# current-sense-v1_0.net
KiCad netlist of a schematic drawn in EAGLE
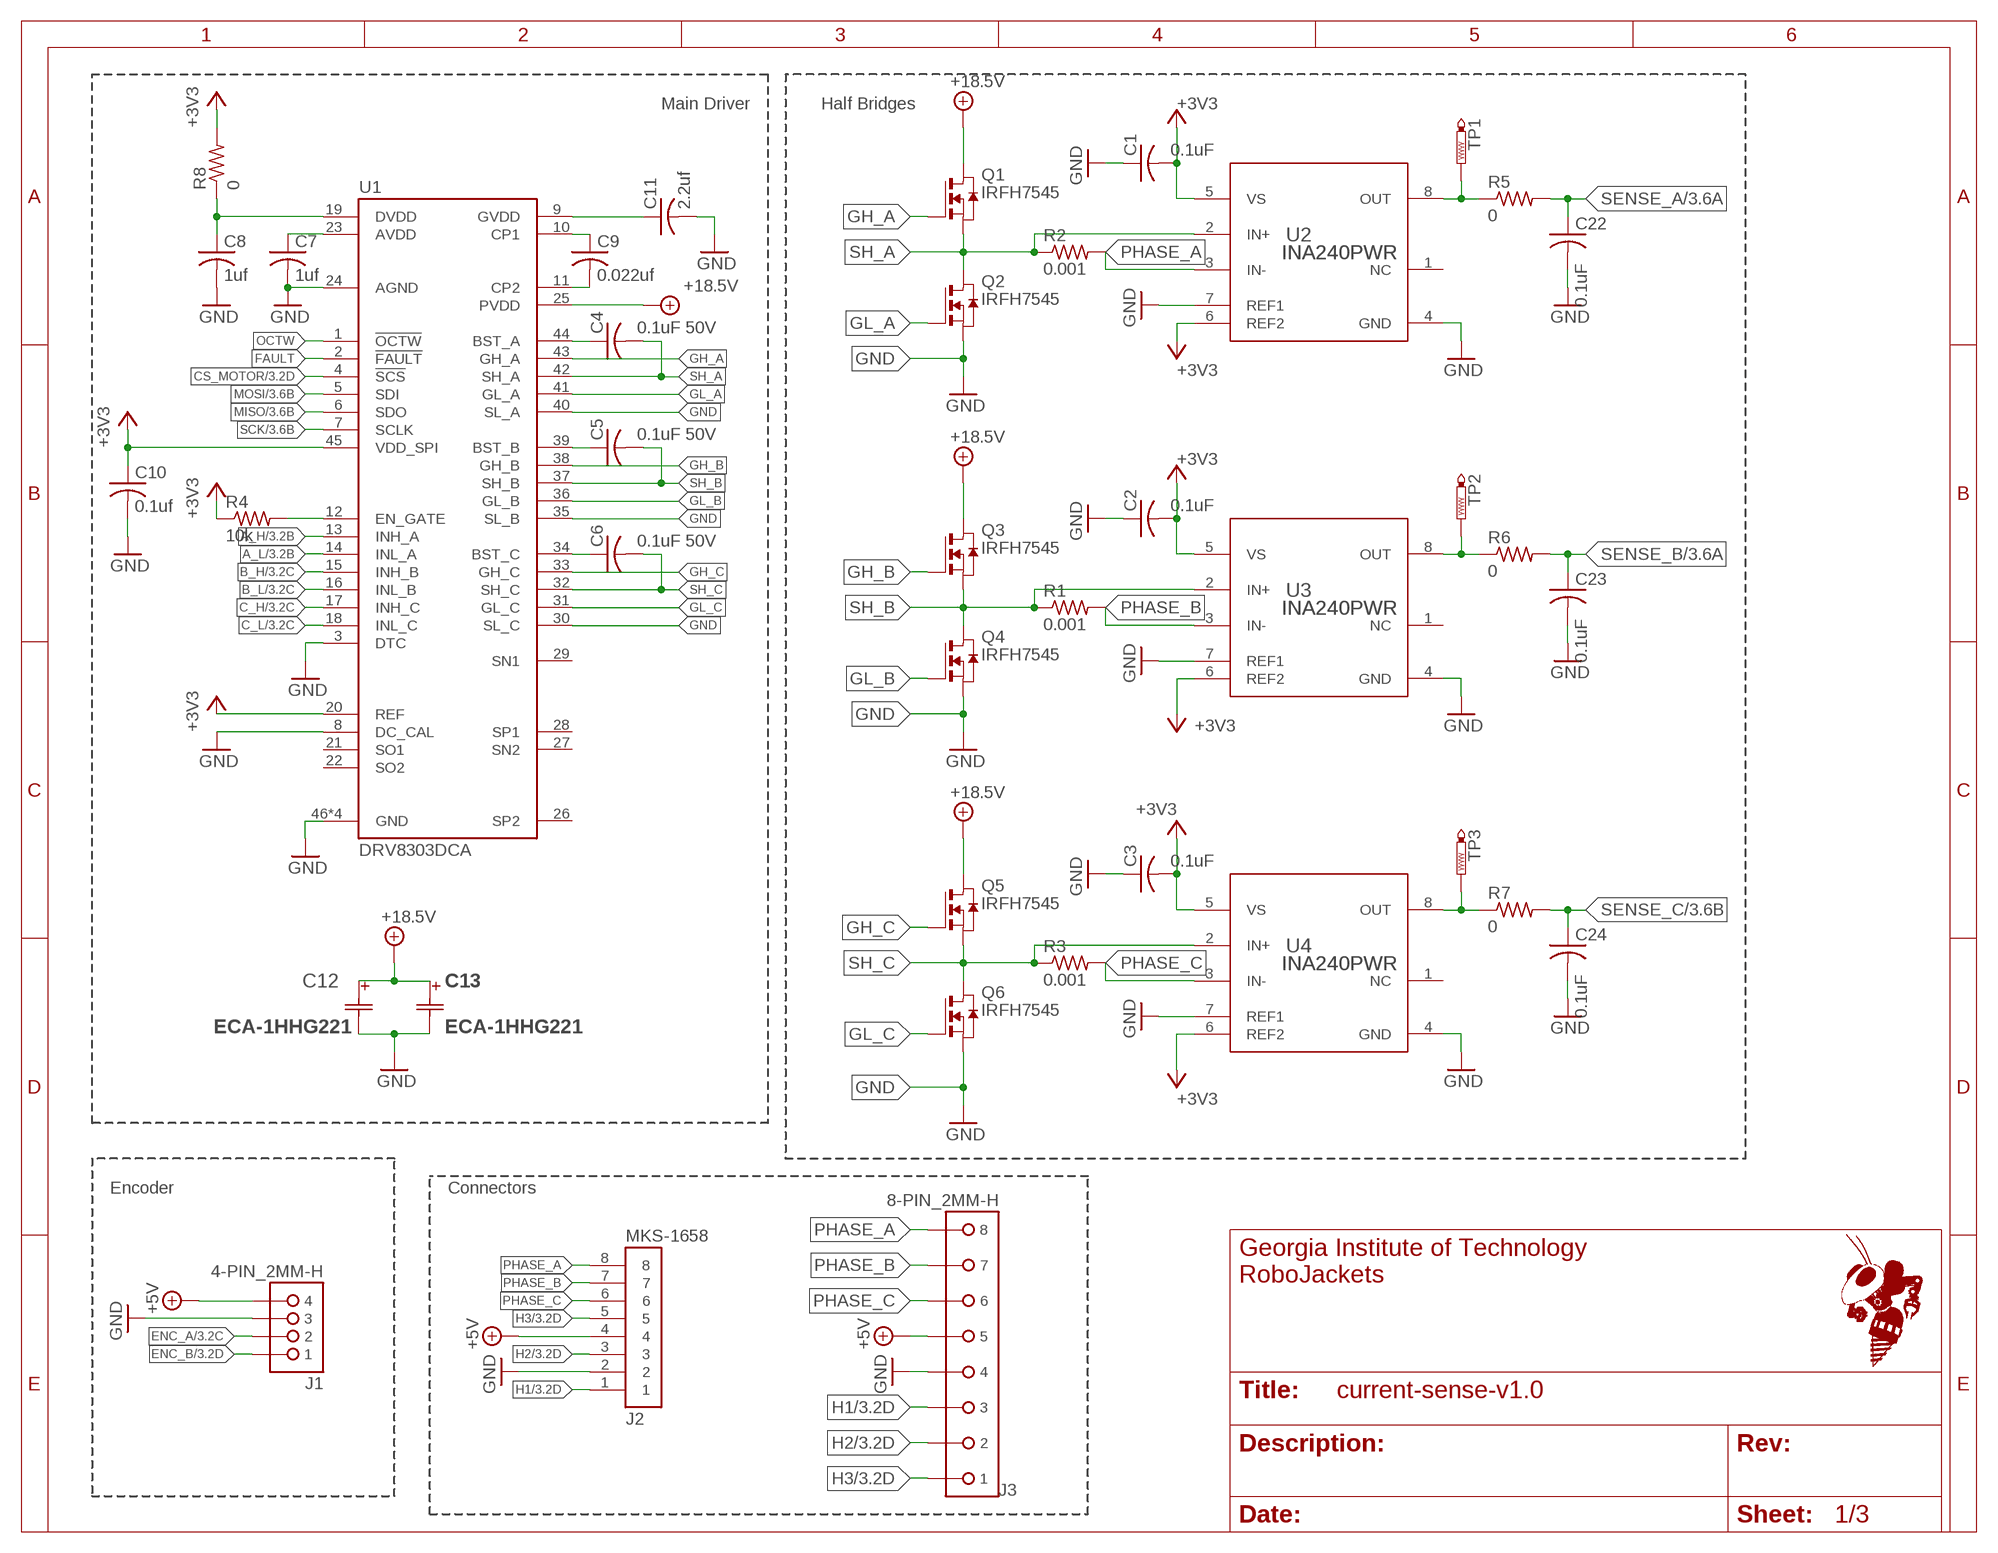
[diagram p0: schematic, sheet 1]
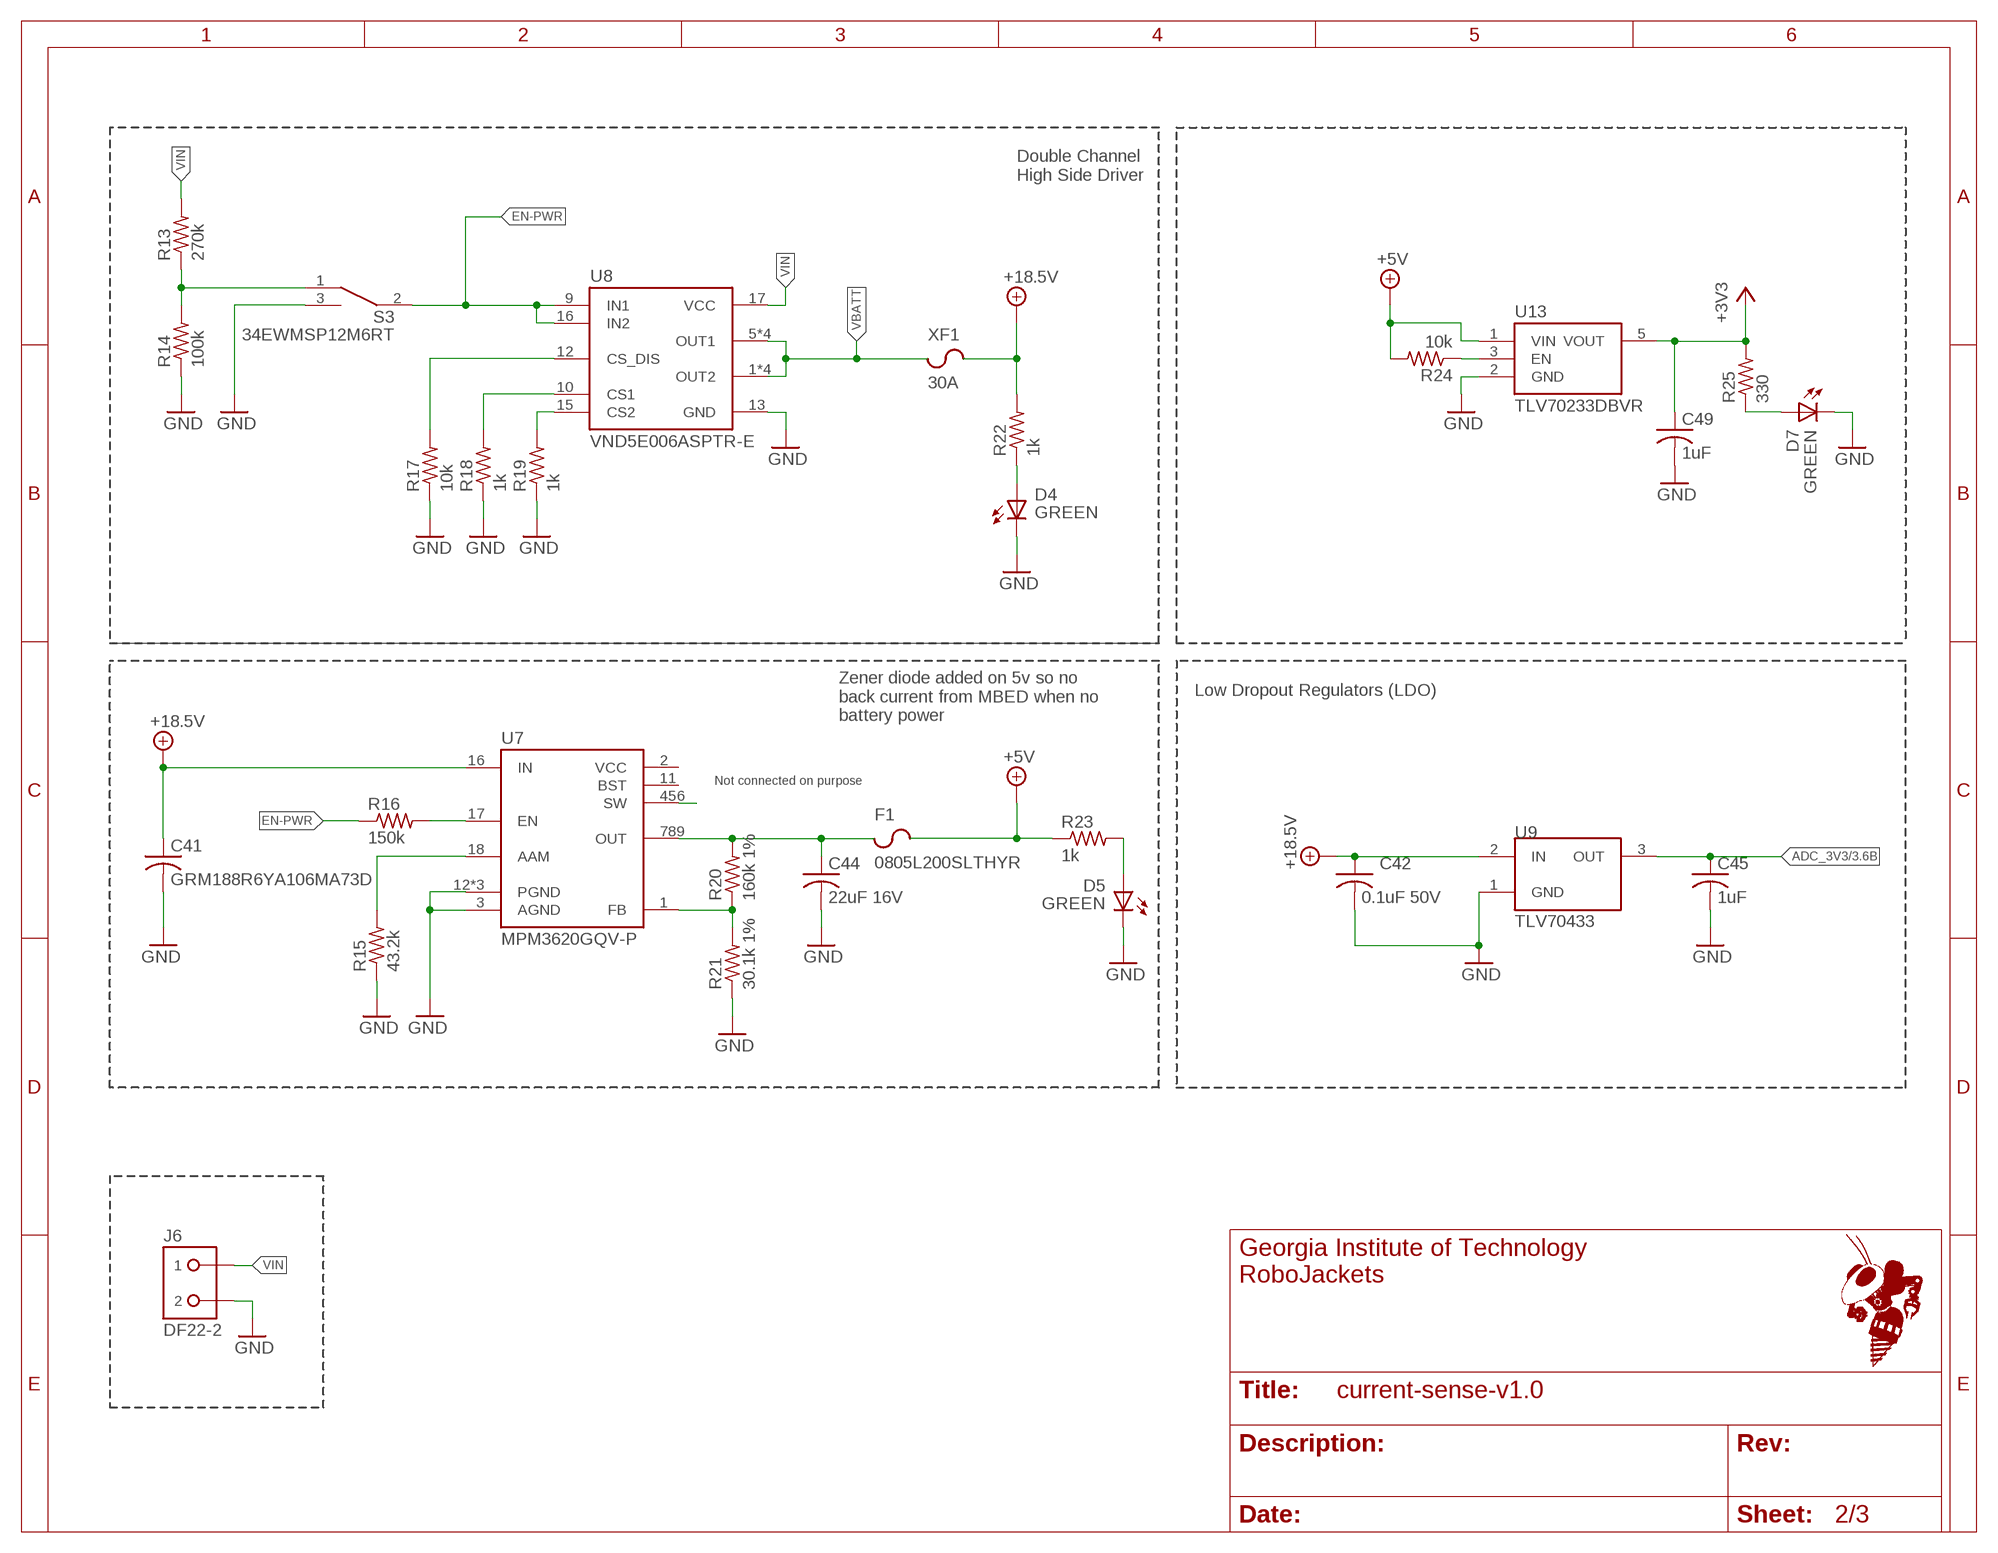
[diagram p1: schematic, sheet 2]
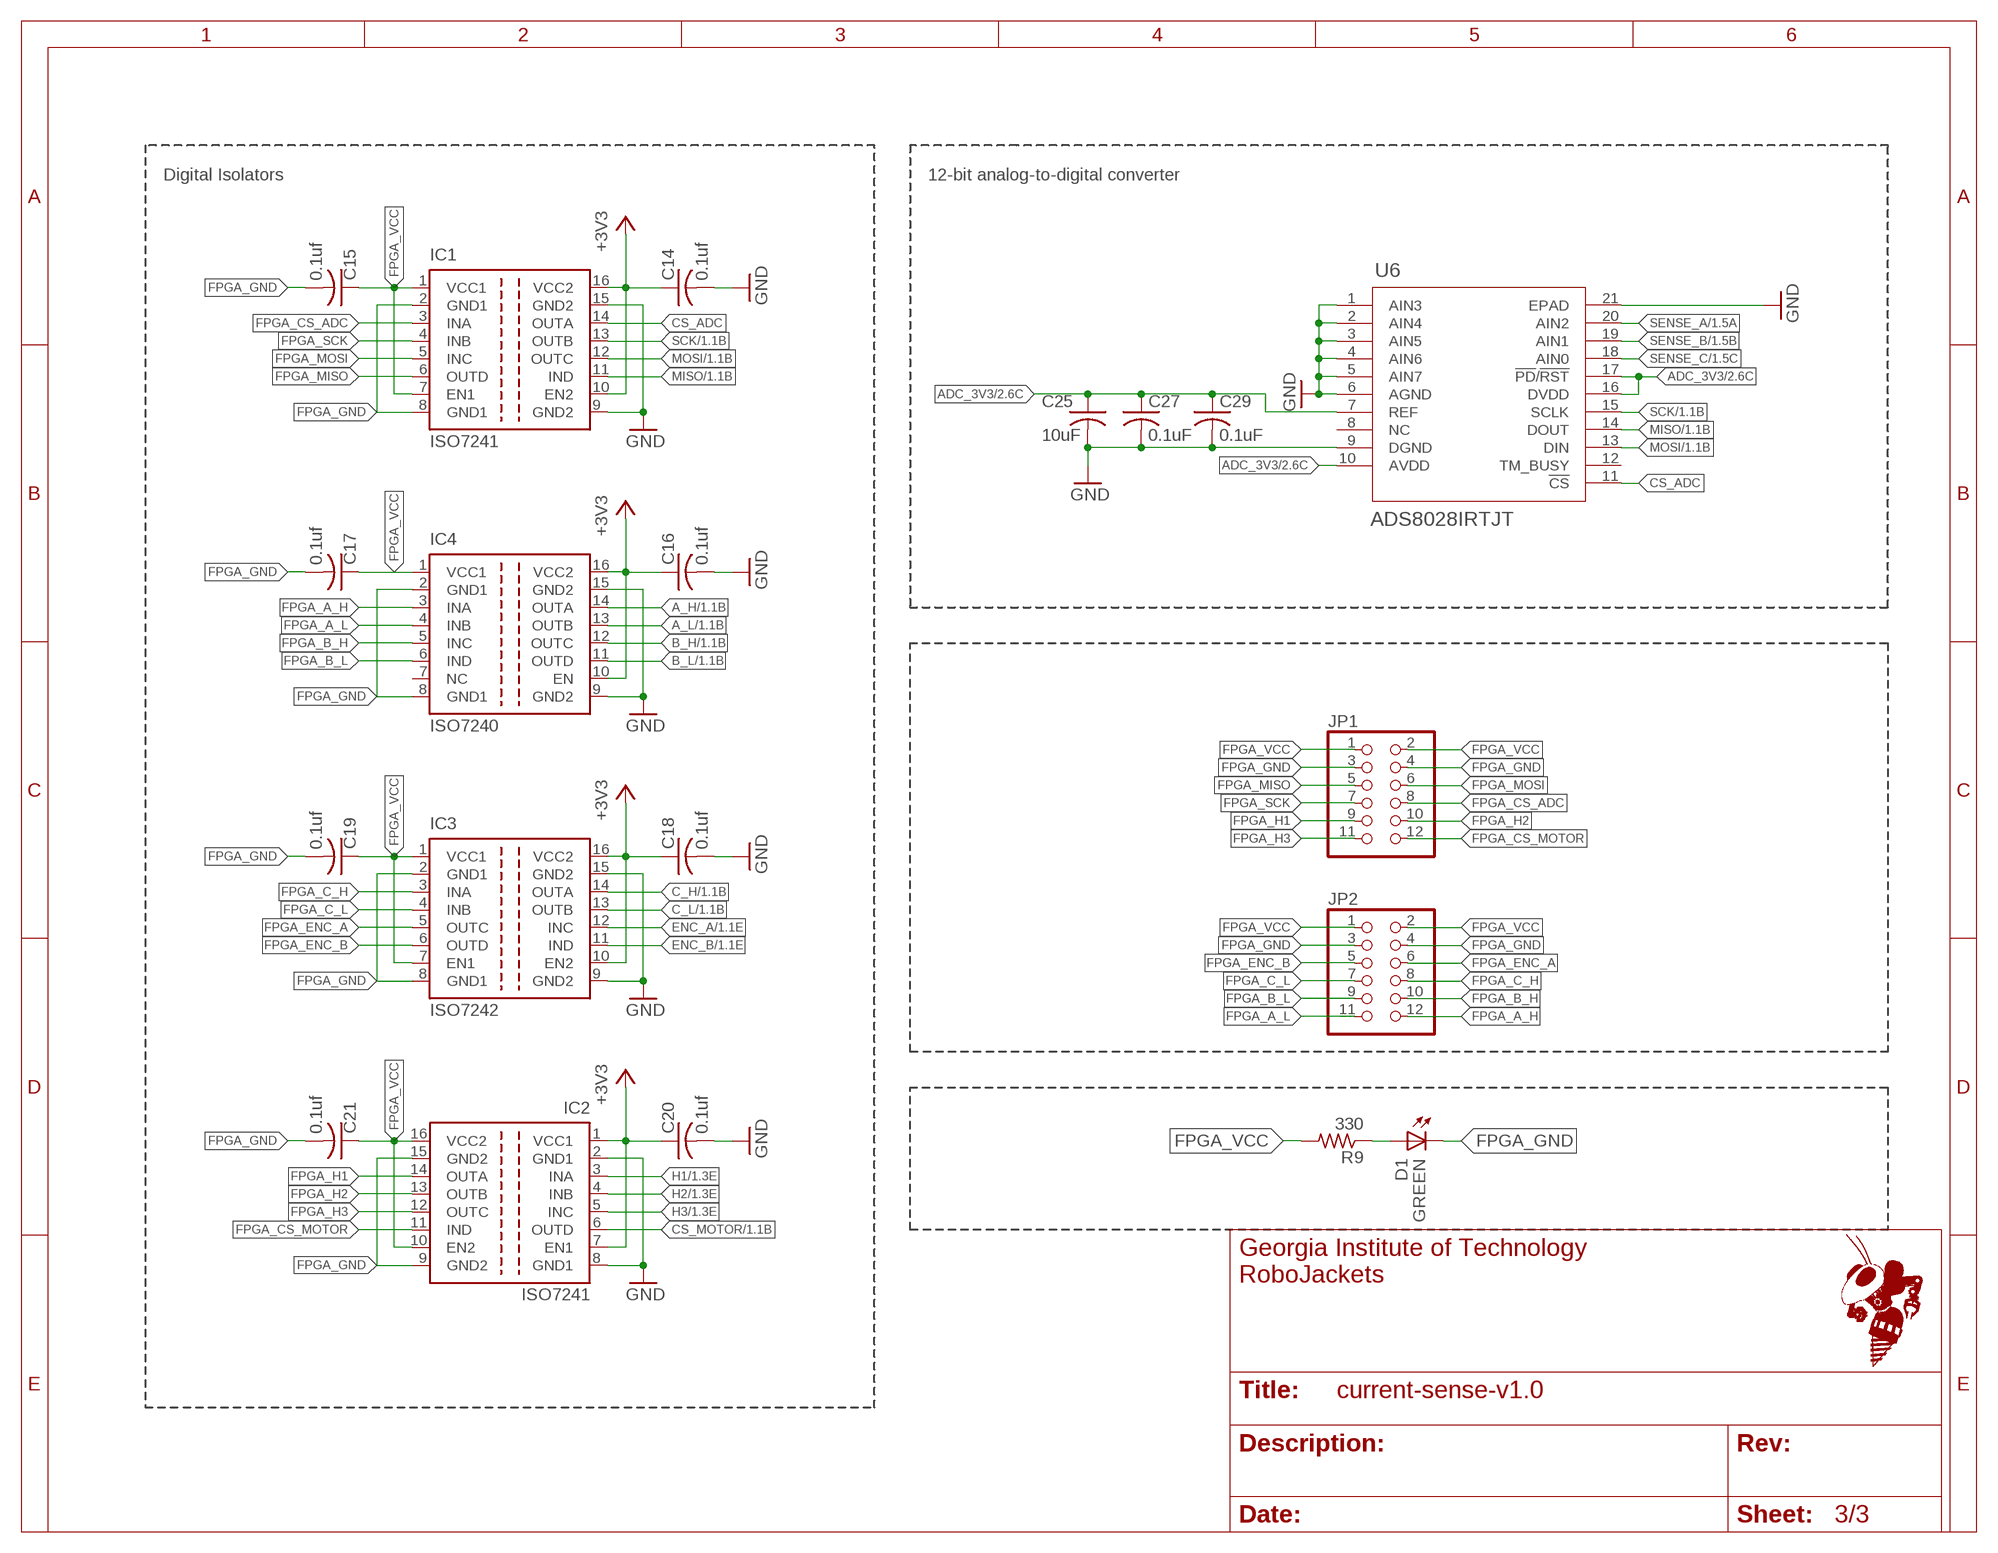
[diagram p2: schematic, sheet 3]

(export (version "E")
  (design (tool "Eeschema 10.0.6"))
  (components
    (comp (ref "C14")
      (value "0.1uf")
      (footprint "eagle-import:C0603")
      (libsource (lib "eagle-import") (part "rcl_334_C-USC0603"))
    )
    (comp (ref "C15")
      (value "0.1uf")
      (footprint "eagle-import:C0603")
      (libsource (lib "eagle-import") (part "rcl_334_C-USC0603"))
    )
    (comp (ref "C16")
      (value "0.1uf")
      (footprint "eagle-import:C0603")
      (libsource (lib "eagle-import") (part "rcl_334_C-USC0603"))
    )
    (comp (ref "C17")
      (value "0.1uf")
      (footprint "eagle-import:C0603")
      (libsource (lib "eagle-import") (part "rcl_334_C-USC0603"))
    )
    (comp (ref "C18")
      (value "0.1uf")
      (footprint "eagle-import:C0603")
      (libsource (lib "eagle-import") (part "rcl_334_C-USC0603"))
    )
    (comp (ref "C19")
      (value "0.1uf")
      (footprint "eagle-import:C0603")
      (libsource (lib "eagle-import") (part "rcl_334_C-USC0603"))
    )
    (comp (ref "C20")
      (value "0.1uf")
      (footprint "eagle-import:C0603")
      (libsource (lib "eagle-import") (part "rcl_334_C-USC0603"))
    )
    (comp (ref "C21")
      (value "0.1uf")
      (footprint "eagle-import:C0603")
      (libsource (lib "eagle-import") (part "rcl_334_C-USC0603"))
    )
    (comp (ref "C25")
      (value "10uF")
      (footprint "eagle-import:C0603")
      (libsource (lib "eagle-import") (part "rcl_334_C-USC0603"))
    )
    (comp (ref "C27")
      (value "0.1uF")
      (footprint "eagle-import:C0603")
      (libsource (lib "eagle-import") (part "rcl_334_C-USC0603"))
    )
    (comp (ref "C29")
      (value "0.1uF")
      (footprint "eagle-import:C0603")
      (libsource (lib "eagle-import") (part "rcl_334_C-USC0603"))
    )
    (comp (ref "D1")
      (value "GREEN")
      (footprint "eagle-import:CHIP-LED0603")
      (fields (field (name "MPN") "LTST-C191KGKT"))
      (libsource (lib "eagle-import") (part "LED-SMD-GREEN"))
    )
    (comp (ref "IC1")
      (value "ISO7241")
      (footprint "eagle-import:SO-16DW")
      (fields (field (name "MPN") "ISO7241CDW"))
      (libsource (lib "eagle-import") (part "ISO7241"))
    )
    (comp (ref "IC2")
      (value "ISO7241")
      (footprint "eagle-import:SO-16DW")
      (fields (field (name "MPN") "ISO7241CDW"))
      (libsource (lib "eagle-import") (part "ISO7241"))
    )
    (comp (ref "IC3")
      (value "ISO7242")
      (footprint "eagle-import:SO-16DW")
      (fields (field (name "MPN") "ISO7242MDW"))
      (libsource (lib "eagle-import") (part "ISO7242"))
    )
    (comp (ref "IC4")
      (value "ISO7240")
      (footprint "eagle-import:SO-16DW")
      (fields (field (name "MPN") "ISO7240MDW"))
      (libsource (lib "eagle-import") (part "ISO7240"))
    )
    (comp (ref "JP1")
      (value "PINHD-2X6/90")
      (footprint "eagle-import:2X06_90")
      (libsource (lib "eagle-import") (part "PINHD-2X6/90"))
    )
    (comp (ref "JP2")
      (value "PINHD-2X6/90")
      (footprint "eagle-import:2X06_90")
      (libsource (lib "eagle-import") (part "PINHD-2X6/90"))
    )
    (comp (ref "R9")
      (value "330")
      (footprint "eagle-import:R0603")
      (libsource (lib "eagle-import") (part "resistor_348_R-US_R0603"))
    )
    (comp (ref "U6")
      (value "ADS8028IRTJT")
      (footprint "eagle-import:RTJ20_2P7X2P7")
      (libsource (lib "eagle-import") (part "ADS8028IRTJT"))
    )
    (comp (ref "C1")
      (value "0.1uF")
      (footprint "eagle-import:C0603")
      (libsource (lib "eagle-import") (part "rcl_334_C-USC0603"))
    )
    (comp (ref "C2")
      (value "0.1uF")
      (footprint "eagle-import:C0603")
      (libsource (lib "eagle-import") (part "rcl_334_C-USC0603"))
    )
    (comp (ref "C3")
      (value "0.1uF")
      (footprint "eagle-import:C0603")
      (libsource (lib "eagle-import") (part "rcl_334_C-USC0603"))
    )
    (comp (ref "C4")
      (value "0.1uF 50V")
      (footprint "eagle-import:C0603")
      (libsource (lib "eagle-import") (part "rcl_334_C-USC0603"))
    )
    (comp (ref "C5")
      (value "0.1uF 50V")
      (footprint "eagle-import:C0603")
      (libsource (lib "eagle-import") (part "rcl_334_C-USC0603"))
    )
    (comp (ref "C6")
      (value "0.1uF 50V")
      (footprint "eagle-import:C0603")
      (libsource (lib "eagle-import") (part "rcl_334_C-USC0603"))
    )
    (comp (ref "C7")
      (value "1uf")
      (footprint "eagle-import:C0603")
      (libsource (lib "eagle-import") (part "rcl_334_C-USC0603"))
    )
    (comp (ref "C8")
      (value "1uf")
      (footprint "eagle-import:C0603")
      (libsource (lib "eagle-import") (part "rcl_334_C-USC0603"))
    )
    (comp (ref "C9")
      (value "0.022uf")
      (footprint "eagle-import:C0603")
      (libsource (lib "eagle-import") (part "rcl_334_C-USC0603"))
    )
    (comp (ref "C10")
      (value "0.1uf")
      (footprint "eagle-import:C0603")
      (libsource (lib "eagle-import") (part "rcl_334_C-USC0603"))
    )
    (comp (ref "C11")
      (value "2.2uf")
      (footprint "eagle-import:C0603")
      (libsource (lib "eagle-import") (part "rcl_334_C-USC0603"))
    )
    (comp (ref "C12")
      (value "ECA-1HHG221")
      (footprint "eagle-import:CAP_PAN_10X12.5")
      (libsource (lib "eagle-import") (part "ECA-1HHG221"))
    )
    (comp (ref "C13")
      (value "ECA-1HHG221")
      (footprint "eagle-import:CAP_PAN_10X12.5")
      (libsource (lib "eagle-import") (part "ECA-1HHG221"))
    )
    (comp (ref "C22")
      (value "0.1uF")
      (footprint "eagle-import:C0603")
      (libsource (lib "eagle-import") (part "rcl_334_C-USC0603"))
    )
    (comp (ref "C23")
      (value "0.1uF")
      (footprint "eagle-import:C0603")
      (libsource (lib "eagle-import") (part "rcl_334_C-USC0603"))
    )
    (comp (ref "C24")
      (value "0.1uF")
      (footprint "eagle-import:C0603")
      (libsource (lib "eagle-import") (part "rcl_334_C-USC0603"))
    )
    (comp (ref "J1")
      (value "4-PIN_2MM-H")
      (footprint "eagle-import:2MM-4-H")
      (fields (field (name "MPN") "0353630460"))
      (libsource (lib "eagle-import") (part "4-PIN_2MM-H"))
    )
    (comp (ref "J2")
      (value "MKS-1658")
      (footprint "eagle-import:MKS-1658")
      (fields (field (name "MPN") "MKS 1658-6-0-808"))
      (libsource (lib "eagle-import") (part "MKS-1658"))
    )
    (comp (ref "J3")
      (value "8-PIN_2MM-H")
      (footprint "eagle-import:2MM-8-H")
      (fields (field (name "MPN") "0353630860"))
      (libsource (lib "eagle-import") (part "8-PIN_2MM-H"))
    )
    (comp (ref "Q1")
      (value "IRFH7545")
      (footprint "eagle-import:PQFN_5X6_E")
      (fields (field (name "MPN") "IRFH7545TRPBF"))
      (libsource (lib "eagle-import") (part "IRFH7545"))
    )
    (comp (ref "Q2")
      (value "IRFH7545")
      (footprint "eagle-import:PQFN_5X6_E")
      (fields (field (name "MPN") "IRFH7545TRPBF"))
      (libsource (lib "eagle-import") (part "IRFH7545"))
    )
    (comp (ref "Q3")
      (value "IRFH7545")
      (footprint "eagle-import:PQFN_5X6_E")
      (fields (field (name "MPN") "IRFH7545TRPBF"))
      (libsource (lib "eagle-import") (part "IRFH7545"))
    )
    (comp (ref "Q4")
      (value "IRFH7545")
      (footprint "eagle-import:PQFN_5X6_E")
      (fields (field (name "MPN") "IRFH7545TRPBF"))
      (libsource (lib "eagle-import") (part "IRFH7545"))
    )
    (comp (ref "Q5")
      (value "IRFH7545")
      (footprint "eagle-import:PQFN_5X6_E")
      (fields (field (name "MPN") "IRFH7545TRPBF"))
      (libsource (lib "eagle-import") (part "IRFH7545"))
    )
    (comp (ref "Q6")
      (value "IRFH7545")
      (footprint "eagle-import:PQFN_5X6_E")
      (fields (field (name "MPN") "IRFH7545TRPBF"))
      (libsource (lib "eagle-import") (part "IRFH7545"))
    )
    (comp (ref "R1")
      (value "0.001")
      (footprint "eagle-import:R2512")
      (libsource (lib "eagle-import") (part "rcl_334_R-US_R2512"))
    )
    (comp (ref "R2")
      (value "0.001")
      (footprint "eagle-import:R2512")
      (libsource (lib "eagle-import") (part "rcl_334_R-US_R2512"))
    )
    (comp (ref "R3")
      (value "0.001")
      (footprint "eagle-import:R2512")
      (libsource (lib "eagle-import") (part "rcl_334_R-US_R2512"))
    )
    (comp (ref "R4")
      (value "10k")
      (footprint "eagle-import:R0603")
      (libsource (lib "eagle-import") (part "rcl_334_R-US_R0603"))
    )
    (comp (ref "R5")
      (value "0")
      (footprint "eagle-import:R0603")
      (libsource (lib "eagle-import") (part "rcl_334_R-US_R0603"))
    )
    (comp (ref "R6")
      (value "0")
      (footprint "eagle-import:R0603")
      (libsource (lib "eagle-import") (part "rcl_334_R-US_R0603"))
    )
    (comp (ref "R7")
      (value "0")
      (footprint "eagle-import:R0603")
      (libsource (lib "eagle-import") (part "rcl_334_R-US_R0603"))
    )
    (comp (ref "R8")
      (value "0")
      (footprint "eagle-import:R0603")
      (libsource (lib "eagle-import") (part "rcl_334_R-US_R0603"))
    )
    (comp (ref "TP1")
      (value "PTR1PAD1-13")
      (footprint "eagle-import:P1-13")
      (libsource (lib "eagle-import") (part "PTR1PAD1-13"))
    )
    (comp (ref "TP2")
      (value "PTR1PAD1-13")
      (footprint "eagle-import:P1-13")
      (libsource (lib "eagle-import") (part "PTR1PAD1-13"))
    )
    (comp (ref "TP3")
      (value "PTR1PAD1-13")
      (footprint "eagle-import:P1-13")
      (libsource (lib "eagle-import") (part "PTR1PAD1-13"))
    )
    (comp (ref "U1")
      (value "DRV8303DCA")
      (footprint "eagle-import:TSSOP-48_PAD")
      (fields (field (name "MPN") "DRV8303DCAR"))
      (libsource (lib "eagle-import") (part "DRV8303DCA"))
    )
    (comp (ref "U2")
      (value "INA240PWR")
      (footprint "eagle-import:PW0008A_N")
      (libsource (lib "eagle-import") (part "INA240PWR"))
    )
    (comp (ref "U3")
      (value "INA240PWR")
      (footprint "eagle-import:PW0008A_N")
      (libsource (lib "eagle-import") (part "INA240PWR"))
    )
    (comp (ref "U4")
      (value "INA240PWR")
      (footprint "eagle-import:PW0008A_N")
      (libsource (lib "eagle-import") (part "INA240PWR"))
    )
    (comp (ref "C41")
      (value "GRM188R6YA106MA73D")
      (footprint "eagle-import:C0603")
      (libsource (lib "eagle-import") (part "C-USC0603"))
    )
    (comp (ref "C42")
      (value "0.1uF 50V")
      (footprint "eagle-import:C0603")
      (libsource (lib "eagle-import") (part "rcl_334_C-USC0603"))
    )
    (comp (ref "C44")
      (value "22uF 16V")
      (footprint "eagle-import:C0805")
      (libsource (lib "eagle-import") (part "rcl_334_C-USC0805"))
    )
    (comp (ref "C45")
      (value "1uF")
      (footprint "eagle-import:C0603")
      (libsource (lib "eagle-import") (part "rcl_334_C-USC0603"))
    )
    (comp (ref "C49")
      (value "1uF")
      (footprint "eagle-import:C0603")
      (libsource (lib "eagle-import") (part "C-USC0603"))
    )
    (comp (ref "D4")
      (value "GREEN")
      (footprint "eagle-import:CHIP-LED0603")
      (fields (field (name "MPN") "LTST-C191KGKT"))
      (libsource (lib "eagle-import") (part "LED-SMD-GREEN"))
    )
    (comp (ref "D5")
      (value "GREEN")
      (footprint "eagle-import:CHIP-LED0603")
      (fields (field (name "MPN") "LTST-C191KGKT"))
      (libsource (lib "eagle-import") (part "LED-SMD-GREEN"))
    )
    (comp (ref "D7")
      (value "GREEN")
      (footprint "eagle-import:CHIP-LED0603")
      (fields (field (name "MPN") "LTST-C191KGKT"))
      (libsource (lib "eagle-import") (part "LED-SMD-GREEN"))
    )
    (comp (ref "F1")
      (value "0805L200SLTHYR")
      (footprint "eagle-import:FUSC2113X75")
      (libsource (lib "eagle-import") (part "CHIP_FUSE0805"))
    )
    (comp (ref "J6")
      (value "DF22-2")
      (footprint "eagle-import:DF22-2-H")
      (fields (field (name "MPN") "DF22-2P-7.92DS(35)"))
      (libsource (lib "eagle-import") (part "DF22-2"))
    )
    (comp (ref "R13")
      (value "270k")
      (footprint "eagle-import:R0603")
      (libsource (lib "eagle-import") (part "R-US_R0603"))
    )
    (comp (ref "R14")
      (value "100k")
      (footprint "eagle-import:R0603")
      (libsource (lib "eagle-import") (part "R-US_R0603"))
    )
    (comp (ref "R15")
      (value "43.2k")
      (footprint "eagle-import:R0603")
      (libsource (lib "eagle-import") (part "rcl_334_R-US_R0603"))
    )
    (comp (ref "R16")
      (value "150k")
      (footprint "eagle-import:R0603")
      (libsource (lib "eagle-import") (part "rcl_334_R-US_R0603"))
    )
    (comp (ref "R17")
      (value "10k")
      (footprint "eagle-import:R0603")
      (libsource (lib "eagle-import") (part "R-US_R0603"))
    )
    (comp (ref "R18")
      (value "1k")
      (footprint "eagle-import:R0603")
      (libsource (lib "eagle-import") (part "R-US_R0603"))
    )
    (comp (ref "R19")
      (value "1k")
      (footprint "eagle-import:R0603")
      (libsource (lib "eagle-import") (part "R-US_R0603"))
    )
    (comp (ref "R20")
      (value "160k 1%")
      (footprint "eagle-import:R0603")
      (libsource (lib "eagle-import") (part "rcl_334_R-US_R0603"))
    )
    (comp (ref "R21")
      (value "30.1k 1%")
      (footprint "eagle-import:R0603")
      (libsource (lib "eagle-import") (part "rcl_334_R-US_R0603"))
    )
    (comp (ref "R22")
      (value "1k")
      (footprint "eagle-import:R0603")
      (libsource (lib "eagle-import") (part "R-US_R0603"))
    )
    (comp (ref "R23")
      (value "1k")
      (footprint "eagle-import:R0603")
      (libsource (lib "eagle-import") (part "resistor_348_R-US_R0603"))
    )
    (comp (ref "R24")
      (value "10k")
      (footprint "eagle-import:R0603")
      (libsource (lib "eagle-import") (part "R-US_R0603"))
    )
    (comp (ref "R25")
      (value "330")
      (footprint "eagle-import:R0603")
      (libsource (lib "eagle-import") (part "resistor_348_R-US_R0603"))
    )
    (comp (ref "S3")
      (value "34EWMSP12M6RT")
      (footprint "eagle-import:34EWMSP12M6RT")
      (libsource (lib "eagle-import") (part "34EWMSP12M6RT"))
    )
    (comp (ref "U7")
      (value "MPM3620GQV-P")
      (footprint "eagle-import:MPM3620GQV-P")
      (libsource (lib "eagle-import") (part "MPM3620GQV-P"))
    )
    (comp (ref "U8")
      (value "VND5E006ASPTR-E")
      (footprint "eagle-import:POWERSO-16")
      (libsource (lib "eagle-import") (part "VND5E006ASPTR-E"))
    )
    (comp (ref "U9")
      (value "TLV70433")
      (footprint "eagle-import:SOT-23-5")
      (libsource (lib "eagle-import") (part "TLV70433"))
    )
    (comp (ref "U13")
      (value "TLV70233DBVR")
      (footprint "eagle-import:SOT-23-5")
      (libsource (lib "eagle-import") (part "TLV70233DBVR"))
    )
    (comp (ref "XF1")
      (value "30A")
      (footprint "eagle-import:3557-2")
      (fields (field (name "MPN") "3557-2"))
      (libsource (lib "eagle-import") (part "3557-2"))
    )
  )
  (nets
    (net (code "1") (name "+3V3") (class "Default")
      (node (ref "C1") (pin "2") (pinfunction "2_2") (pintype "passive"))
      (node (ref "C10") (pin "1") (pinfunction "1_1") (pintype "passive"))
      (node (ref "C14") (pin "1") (pinfunction "1_1") (pintype "passive"))
      (node (ref "C16") (pin "1") (pinfunction "1_1") (pintype "passive"))
      (node (ref "C18") (pin "1") (pinfunction "1_1") (pintype "passive"))
      (node (ref "C2") (pin "2") (pinfunction "2_2") (pintype "passive"))
      (node (ref "C20") (pin "1") (pinfunction "1_1") (pintype "passive"))
      (node (ref "C3") (pin "2") (pinfunction "2_2") (pintype "passive"))
      (node (ref "C49") (pin "1") (pinfunction "1_1") (pintype "passive"))
      (node (ref "IC1") (pin "10") (pinfunction "EN2_10") (pintype "input"))
      (node (ref "IC1") (pin "16") (pinfunction "VCC2_16") (pintype "power_in"))
      (node (ref "IC2") (pin "1") (pinfunction "VCC1_1") (pintype "power_in"))
      (node (ref "IC2") (pin "7") (pinfunction "EN1_7") (pintype "input"))
      (node (ref "IC3") (pin "10") (pinfunction "EN2_10") (pintype "input"))
      (node (ref "IC3") (pin "16") (pinfunction "VCC2_16") (pintype "power_in"))
      (node (ref "IC4") (pin "10") (pinfunction "EN_10") (pintype "input"))
      (node (ref "IC4") (pin "16") (pinfunction "VCC2_16") (pintype "power_in"))
      (node (ref "R25") (pin "2") (pinfunction "2_2") (pintype "passive"))
      (node (ref "R4") (pin "1") (pinfunction "1_1") (pintype "passive"))
      (node (ref "R8") (pin "2") (pinfunction "2_2") (pintype "passive"))
      (node (ref "U1") (pin "20") (pinfunction "REF_20") (pintype "bidirectional"))
      (node (ref "U1") (pin "45") (pinfunction "VDD_SPI_45") (pintype "bidirectional"))
      (node (ref "U13") (pin "5") (pinfunction "VOUT_5") (pintype "bidirectional"))
      (node (ref "U2") (pin "5") (pinfunction "VS_5") (pintype "power_in"))
      (node (ref "U2") (pin "6") (pinfunction "REF2_6") (pintype "input"))
      (node (ref "U3") (pin "5") (pinfunction "VS_5") (pintype "power_in"))
      (node (ref "U3") (pin "6") (pinfunction "REF2_6") (pintype "input"))
      (node (ref "U4") (pin "5") (pinfunction "VS_5") (pintype "power_in"))
      (node (ref "U4") (pin "6") (pinfunction "REF2_6") (pintype "input"))
    )
    (net (code "2") (name "+5V") (class "Default")
      (node (ref "F1") (pin "2") (pinfunction "2_2") (pintype "bidirectional"))
      (node (ref "J1") (pin "4") (pinfunction "4_4") (pintype "passive"))
      (node (ref "J2") (pin "4") (pinfunction "4_4") (pintype "bidirectional"))
      (node (ref "J3") (pin "5") (pinfunction "5_5") (pintype "passive"))
      (node (ref "R23") (pin "1") (pinfunction "1_1") (pintype "passive"))
      (node (ref "R24") (pin "2") (pinfunction "2_2") (pintype "passive"))
      (node (ref "U13") (pin "1") (pinfunction "VIN_1") (pintype "bidirectional"))
    )
    (net (code "3") (name "+18.5V") (class "Default")
      (node (ref "C12") (pin "1") (pinfunction "11_1") (pintype "passive"))
      (node (ref "C13") (pin "1") (pinfunction "11_1") (pintype "passive"))
      (node (ref "C41") (pin "1") (pinfunction "1_1") (pintype "passive"))
      (node (ref "C42") (pin "1") (pinfunction "1_1") (pintype "passive"))
      (node (ref "Q1") (pin "5678") (pinfunction "D_5678") (pintype "passive"))
      (node (ref "Q3") (pin "5678") (pinfunction "D_5678") (pintype "passive"))
      (node (ref "Q5") (pin "5678") (pinfunction "D_5678") (pintype "passive"))
      (node (ref "R22") (pin "2") (pinfunction "2_2") (pintype "passive"))
      (node (ref "U1") (pin "25") (pinfunction "PVDD_25") (pintype "bidirectional"))
      (node (ref "U7") (pin "16") (pinfunction "IN_16") (pintype "bidirectional"))
      (node (ref "U9") (pin "2") (pinfunction "IN_2") (pintype "input"))
      (node (ref "XF1") (pin "3") (pinfunction "2_3") (pintype "bidirectional"))
      (node (ref "XF1") (pin "4") (pinfunction "2_4") (pintype "bidirectional"))
    )
    (net (code "4") (name "ADC_3V3") (class "Default")
      (node (ref "C25") (pin "1") (pinfunction "1_1") (pintype "passive"))
      (node (ref "C27") (pin "1") (pinfunction "1_1") (pintype "passive"))
      (node (ref "C29") (pin "1") (pinfunction "1_1") (pintype "passive"))
      (node (ref "C45") (pin "1") (pinfunction "1_1") (pintype "passive"))
      (node (ref "U6") (pin "10") (pinfunction "AVDD_10") (pintype "power_in"))
      (node (ref "U6") (pin "16") (pinfunction "DVDD_16") (pintype "power_in"))
      (node (ref "U6") (pin "17") (pinfunction "~{PD}/~{RST}_17") (pintype "input"))
      (node (ref "U6") (pin "7") (pinfunction "REF_7") (pintype "bidirectional"))
      (node (ref "U9") (pin "3") (pinfunction "OUT_3") (pintype "output"))
    )
    (net (code "5") (name "A_H") (class "Default")
      (node (ref "IC4") (pin "14") (pinfunction "OUTA_14") (pintype "output"))
      (node (ref "U1") (pin "13") (pinfunction "INH_A_13") (pintype "bidirectional"))
    )
    (net (code "6") (name "A_L") (class "Default")
      (node (ref "IC4") (pin "13") (pinfunction "OUTB_13") (pintype "output"))
      (node (ref "U1") (pin "14") (pinfunction "INL_A_14") (pintype "bidirectional"))
    )
    (net (code "7") (name "B_H") (class "Default")
      (node (ref "IC4") (pin "12") (pinfunction "OUTC_12") (pintype "output"))
      (node (ref "U1") (pin "15") (pinfunction "INH_B_15") (pintype "bidirectional"))
    )
    (net (code "8") (name "B_L") (class "Default")
      (node (ref "IC4") (pin "11") (pinfunction "OUTD_11") (pintype "output"))
      (node (ref "U1") (pin "16") (pinfunction "INL_B_16") (pintype "bidirectional"))
    )
    (net (code "9") (name "CS_ADC") (class "Default")
      (node (ref "IC1") (pin "14") (pinfunction "OUTA_14") (pintype "output"))
      (node (ref "U6") (pin "11") (pinfunction "~{CS}_11") (pintype "input"))
    )
    (net (code "10") (name "CS_MOTOR") (class "Default")
      (node (ref "IC2") (pin "6") (pinfunction "OUTD_6") (pintype "output"))
      (node (ref "U1") (pin "4") (pinfunction "~{SCS}_4") (pintype "bidirectional"))
    )
    (net (code "11") (name "C_H") (class "Default")
      (node (ref "IC3") (pin "14") (pinfunction "OUTA_14") (pintype "output"))
      (node (ref "U1") (pin "17") (pinfunction "INH_C_17") (pintype "bidirectional"))
    )
    (net (code "12") (name "C_L") (class "Default")
      (node (ref "IC3") (pin "13") (pinfunction "OUTB_13") (pintype "output"))
      (node (ref "U1") (pin "18") (pinfunction "INL_C_18") (pintype "bidirectional"))
    )
    (net (code "13") (name "EN-PWR") (class "Default")
      (node (ref "R16") (pin "1") (pinfunction "1_1") (pintype "passive"))
      (node (ref "S3") (pin "2") (pinfunction "COMMON_2") (pintype "bidirectional"))
      (node (ref "U8") (pin "16") (pinfunction "IN2_16") (pintype "bidirectional"))
      (node (ref "U8") (pin "9") (pinfunction "IN1_9") (pintype "bidirectional"))
    )
    (net (code "14") (name "ENC_A") (class "Default")
      (node (ref "IC3") (pin "12") (pinfunction "INC_12") (pintype "input"))
      (node (ref "J1") (pin "2") (pinfunction "2_2") (pintype "passive"))
    )
    (net (code "15") (name "ENC_B") (class "Default")
      (node (ref "IC3") (pin "11") (pinfunction "IND_11") (pintype "input"))
      (node (ref "J1") (pin "1") (pinfunction "1_1") (pintype "passive"))
    )
    (net (code "16") (name "FAULT") (class "Default")
      (node (ref "U1") (pin "2") (pinfunction "~{FAULT}_2") (pintype "bidirectional"))
    )
    (net (code "17") (name "FPGA_A_H") (class "Default")
      (node (ref "IC4") (pin "3") (pinfunction "INA_3") (pintype "input"))
      (node (ref "JP2") (pin "12") (pinfunction "12_12") (pintype "passive"))
    )
    (net (code "18") (name "FPGA_A_L") (class "Default")
      (node (ref "IC4") (pin "4") (pinfunction "INB_4") (pintype "input"))
      (node (ref "JP2") (pin "11") (pinfunction "11_11") (pintype "passive"))
    )
    (net (code "19") (name "FPGA_B_H") (class "Default")
      (node (ref "IC4") (pin "5") (pinfunction "INC_5") (pintype "input"))
      (node (ref "JP2") (pin "10") (pinfunction "10_10") (pintype "passive"))
    )
    (net (code "20") (name "FPGA_B_L") (class "Default")
      (node (ref "IC4") (pin "6") (pinfunction "IND_6") (pintype "input"))
      (node (ref "JP2") (pin "9") (pinfunction "9_9") (pintype "passive"))
    )
    (net (code "21") (name "FPGA_CS_ADC") (class "Default")
      (node (ref "IC1") (pin "3") (pinfunction "INA_3") (pintype "input"))
      (node (ref "JP1") (pin "8") (pinfunction "8_8") (pintype "passive"))
    )
    (net (code "22") (name "FPGA_CS_MOTOR") (class "Default")
      (node (ref "IC2") (pin "11") (pinfunction "IND_11") (pintype "input"))
      (node (ref "JP1") (pin "12") (pinfunction "12_12") (pintype "passive"))
    )
    (net (code "23") (name "FPGA_C_H") (class "Default")
      (node (ref "IC3") (pin "3") (pinfunction "INA_3") (pintype "input"))
      (node (ref "JP2") (pin "8") (pinfunction "8_8") (pintype "passive"))
    )
    (net (code "24") (name "FPGA_C_L") (class "Default")
      (node (ref "IC3") (pin "4") (pinfunction "INB_4") (pintype "input"))
      (node (ref "JP2") (pin "7") (pinfunction "7_7") (pintype "passive"))
    )
    (net (code "25") (name "FPGA_ENC_A") (class "Default")
      (node (ref "IC3") (pin "5") (pinfunction "OUTC_5") (pintype "output"))
      (node (ref "JP2") (pin "6") (pinfunction "6_6") (pintype "passive"))
    )
    (net (code "26") (name "FPGA_ENC_B") (class "Default")
      (node (ref "IC3") (pin "6") (pinfunction "OUTD_6") (pintype "output"))
      (node (ref "JP2") (pin "5") (pinfunction "5_5") (pintype "passive"))
    )
    (net (code "27") (name "FPGA_GND") (class "Default")
      (node (ref "C15") (pin "2") (pinfunction "2_2") (pintype "passive"))
      (node (ref "C17") (pin "2") (pinfunction "2_2") (pintype "passive"))
      (node (ref "C19") (pin "2") (pinfunction "2_2") (pintype "passive"))
      (node (ref "C21") (pin "2") (pinfunction "2_2") (pintype "passive"))
      (node (ref "D1") (pin "C") (pinfunction "K_C") (pintype "passive"))
      (node (ref "IC1") (pin "2") (pinfunction "GND1_2") (pintype "power_in"))
      (node (ref "IC1") (pin "8") (pinfunction "GND1_8") (pintype "power_in"))
      (node (ref "IC2") (pin "15") (pinfunction "GND2_15") (pintype "power_in"))
      (node (ref "IC2") (pin "9") (pinfunction "GND2_9") (pintype "power_in"))
      (node (ref "IC3") (pin "2") (pinfunction "GND1_2") (pintype "power_in"))
      (node (ref "IC3") (pin "8") (pinfunction "GND1_8") (pintype "power_in"))
      (node (ref "IC4") (pin "2") (pinfunction "GND1_2") (pintype "power_in"))
      (node (ref "IC4") (pin "8") (pinfunction "GND1_8") (pintype "power_in"))
      (node (ref "JP1") (pin "3") (pinfunction "3_3") (pintype "passive"))
      (node (ref "JP1") (pin "4") (pinfunction "4_4") (pintype "passive"))
      (node (ref "JP2") (pin "3") (pinfunction "3_3") (pintype "passive"))
      (node (ref "JP2") (pin "4") (pinfunction "4_4") (pintype "passive"))
    )
    (net (code "28") (name "FPGA_H1") (class "Default")
      (node (ref "IC2") (pin "14") (pinfunction "OUTA_14") (pintype "output"))
      (node (ref "JP1") (pin "9") (pinfunction "9_9") (pintype "passive"))
    )
    (net (code "29") (name "FPGA_H2") (class "Default")
      (node (ref "IC2") (pin "13") (pinfunction "OUTB_13") (pintype "output"))
      (node (ref "JP1") (pin "10") (pinfunction "10_10") (pintype "passive"))
    )
    (net (code "30") (name "FPGA_H3") (class "Default")
      (node (ref "IC2") (pin "12") (pinfunction "OUTC_12") (pintype "output"))
      (node (ref "JP1") (pin "11") (pinfunction "11_11") (pintype "passive"))
    )
    (net (code "31") (name "FPGA_MISO") (class "Default")
      (node (ref "IC1") (pin "6") (pinfunction "OUTD_6") (pintype "output"))
      (node (ref "JP1") (pin "5") (pinfunction "5_5") (pintype "passive"))
    )
    (net (code "32") (name "FPGA_MOSI") (class "Default")
      (node (ref "IC1") (pin "5") (pinfunction "INC_5") (pintype "input"))
      (node (ref "JP1") (pin "6") (pinfunction "6_6") (pintype "passive"))
    )
    (net (code "33") (name "FPGA_SCK") (class "Default")
      (node (ref "IC1") (pin "4") (pinfunction "INB_4") (pintype "input"))
      (node (ref "JP1") (pin "7") (pinfunction "7_7") (pintype "passive"))
    )
    (net (code "34") (name "FPGA_VCC") (class "Default")
      (node (ref "C15") (pin "1") (pinfunction "1_1") (pintype "passive"))
      (node (ref "C17") (pin "1") (pinfunction "1_1") (pintype "passive"))
      (node (ref "C19") (pin "1") (pinfunction "1_1") (pintype "passive"))
      (node (ref "C21") (pin "1") (pinfunction "1_1") (pintype "passive"))
      (node (ref "IC1") (pin "1") (pinfunction "VCC1_1") (pintype "power_in"))
      (node (ref "IC1") (pin "7") (pinfunction "EN1_7") (pintype "input"))
      (node (ref "IC2") (pin "10") (pinfunction "EN2_10") (pintype "input"))
      (node (ref "IC2") (pin "16") (pinfunction "VCC2_16") (pintype "power_in"))
      (node (ref "IC3") (pin "1") (pinfunction "VCC1_1") (pintype "power_in"))
      (node (ref "IC3") (pin "7") (pinfunction "EN1_7") (pintype "input"))
      (node (ref "IC4") (pin "1") (pinfunction "VCC1_1") (pintype "power_in"))
      (node (ref "JP1") (pin "1") (pinfunction "1_1") (pintype "passive"))
      (node (ref "JP1") (pin "2") (pinfunction "2_2") (pintype "passive"))
      (node (ref "JP2") (pin "1") (pinfunction "1_1") (pintype "passive"))
      (node (ref "JP2") (pin "2") (pinfunction "2_2") (pintype "passive"))
      (node (ref "R9") (pin "2") (pinfunction "2_2") (pintype "passive"))
    )
    (net (code "35") (name "GH_A") (class "Default")
      (node (ref "Q1") (pin "4") (pinfunction "G_4") (pintype "passive"))
      (node (ref "U1") (pin "43") (pinfunction "GH_A_43") (pintype "bidirectional"))
    )
    (net (code "36") (name "GH_B") (class "Default")
      (node (ref "Q3") (pin "4") (pinfunction "G_4") (pintype "passive"))
      (node (ref "U1") (pin "38") (pinfunction "GH_B_38") (pintype "bidirectional"))
    )
    (net (code "37") (name "GH_C") (class "Default")
      (node (ref "Q5") (pin "4") (pinfunction "G_4") (pintype "passive"))
      (node (ref "U1") (pin "33") (pinfunction "GH_C_33") (pintype "bidirectional"))
    )
    (net (code "38") (name "GL_A") (class "Default")
      (node (ref "Q2") (pin "4") (pinfunction "G_4") (pintype "passive"))
      (node (ref "U1") (pin "41") (pinfunction "GL_A_41") (pintype "bidirectional"))
    )
    (net (code "39") (name "GL_B") (class "Default")
      (node (ref "Q4") (pin "4") (pinfunction "G_4") (pintype "passive"))
      (node (ref "U1") (pin "36") (pinfunction "GL_B_36") (pintype "bidirectional"))
    )
    (net (code "40") (name "GL_C") (class "Default")
      (node (ref "Q6") (pin "4") (pinfunction "G_4") (pintype "passive"))
      (node (ref "U1") (pin "31") (pinfunction "GL_C_31") (pintype "bidirectional"))
    )
    (net (code "41") (name "GND") (class "Default")
      (node (ref "C1") (pin "1") (pinfunction "1_1") (pintype "passive"))
      (node (ref "C10") (pin "2") (pinfunction "2_2") (pintype "passive"))
      (node (ref "C11") (pin "2") (pinfunction "2_2") (pintype "passive"))
      (node (ref "C12") (pin "2") (pinfunction "22_2") (pintype "passive"))
      (node (ref "C13") (pin "2") (pinfunction "22_2") (pintype "passive"))
      (node (ref "C14") (pin "2") (pinfunction "2_2") (pintype "passive"))
      (node (ref "C16") (pin "2") (pinfunction "2_2") (pintype "passive"))
      (node (ref "C18") (pin "2") (pinfunction "2_2") (pintype "passive"))
      (node (ref "C2") (pin "1") (pinfunction "1_1") (pintype "passive"))
      (node (ref "C20") (pin "2") (pinfunction "2_2") (pintype "passive"))
      (node (ref "C22") (pin "2") (pinfunction "2_2") (pintype "passive"))
      (node (ref "C23") (pin "2") (pinfunction "2_2") (pintype "passive"))
      (node (ref "C24") (pin "2") (pinfunction "2_2") (pintype "passive"))
      (node (ref "C25") (pin "2") (pinfunction "2_2") (pintype "passive"))
      (node (ref "C27") (pin "2") (pinfunction "2_2") (pintype "passive"))
      (node (ref "C29") (pin "2") (pinfunction "2_2") (pintype "passive"))
      (node (ref "C3") (pin "1") (pinfunction "1_1") (pintype "passive"))
      (node (ref "C41") (pin "2") (pinfunction "2_2") (pintype "passive"))
      (node (ref "C42") (pin "2") (pinfunction "2_2") (pintype "passive"))
      (node (ref "C44") (pin "2") (pinfunction "2_2") (pintype "passive"))
      (node (ref "C45") (pin "2") (pinfunction "2_2") (pintype "passive"))
      (node (ref "C49") (pin "2") (pinfunction "2_2") (pintype "passive"))
      (node (ref "C7") (pin "2") (pinfunction "2_2") (pintype "passive"))
      (node (ref "C8") (pin "2") (pinfunction "2_2") (pintype "passive"))
      (node (ref "D4") (pin "C") (pinfunction "K_C") (pintype "passive"))
      (node (ref "D5") (pin "C") (pinfunction "K_C") (pintype "passive"))
      (node (ref "D7") (pin "C") (pinfunction "K_C") (pintype "passive"))
      (node (ref "IC1") (pin "15") (pinfunction "GND2_15") (pintype "power_in"))
      (node (ref "IC1") (pin "9") (pinfunction "GND2_9") (pintype "power_in"))
      (node (ref "IC2") (pin "2") (pinfunction "GND1_2") (pintype "power_in"))
      (node (ref "IC2") (pin "8") (pinfunction "GND1_8") (pintype "power_in"))
      (node (ref "IC3") (pin "15") (pinfunction "GND2_15") (pintype "power_in"))
      (node (ref "IC3") (pin "9") (pinfunction "GND2_9") (pintype "power_in"))
      (node (ref "IC4") (pin "15") (pinfunction "GND2_15") (pintype "power_in"))
      (node (ref "IC4") (pin "9") (pinfunction "GND2_9") (pintype "power_in"))
      (node (ref "J1") (pin "3") (pinfunction "3_3") (pintype "passive"))
      (node (ref "J2") (pin "2") (pinfunction "2_2") (pintype "bidirectional"))
      (node (ref "J3") (pin "4") (pinfunction "4_4") (pintype "passive"))
      (node (ref "J6") (pin "2") (pinfunction "2_2") (pintype "bidirectional"))
      (node (ref "Q2") (pin "1") (pinfunction "S_1") (pintype "passive"))
      (node (ref "Q2") (pin "2") (pinfunction "S_2") (pintype "passive"))
      (node (ref "Q2") (pin "3") (pinfunction "S_3") (pintype "passive"))
      (node (ref "Q4") (pin "1") (pinfunction "S_1") (pintype "passive"))
      (node (ref "Q4") (pin "2") (pinfunction "S_2") (pintype "passive"))
      (node (ref "Q4") (pin "3") (pinfunction "S_3") (pintype "passive"))
      (node (ref "Q6") (pin "1") (pinfunction "S_1") (pintype "passive"))
      (node (ref "Q6") (pin "2") (pinfunction "S_2") (pintype "passive"))
      (node (ref "Q6") (pin "3") (pinfunction "S_3") (pintype "passive"))
      (node (ref "R14") (pin "1") (pinfunction "1_1") (pintype "passive"))
      (node (ref "R15") (pin "1") (pinfunction "1_1") (pintype "passive"))
      (node (ref "R17") (pin "1") (pinfunction "1_1") (pintype "passive"))
      (node (ref "R18") (pin "1") (pinfunction "1_1") (pintype "passive"))
      (node (ref "R19") (pin "1") (pinfunction "1_1") (pintype "passive"))
      (node (ref "R21") (pin "1") (pinfunction "1_1") (pintype "passive"))
      (node (ref "S3") (pin "3") (pinfunction "B_3") (pintype "bidirectional"))
      (node (ref "U1") (pin "24") (pinfunction "AGND_24") (pintype "bidirectional"))
      (node (ref "U1") (pin "3") (pinfunction "DTC_3") (pintype "bidirectional"))
      (node (ref "U1") (pin "30") (pinfunction "SL_C_30") (pintype "bidirectional"))
      (node (ref "U1") (pin "35") (pinfunction "SL_B_35") (pintype "bidirectional"))
      (node (ref "U1") (pin "40") (pinfunction "SL_A_40") (pintype "bidirectional"))
      (node (ref "U1") (pin "46") (pinfunction "GND_46") (pintype "bidirectional"))
      (node (ref "U1") (pin "47") (pinfunction "GND_47") (pintype "bidirectional"))
      (node (ref "U1") (pin "48") (pinfunction "GND_48") (pintype "bidirectional"))
      (node (ref "U1") (pin "8") (pinfunction "DC_CAL_8") (pintype "bidirectional"))
      (node (ref "U1") (pin "PAD") (pinfunction "GND_PAD") (pintype "bidirectional"))
      (node (ref "U13") (pin "2") (pinfunction "GND_2") (pintype "bidirectional"))
      (node (ref "U2") (pin "4") (pinfunction "GND_4") (pintype "power_in"))
      (node (ref "U2") (pin "7") (pinfunction "REF1_7") (pintype "input"))
      (node (ref "U3") (pin "4") (pinfunction "GND_4") (pintype "power_in"))
      (node (ref "U3") (pin "7") (pinfunction "REF1_7") (pintype "input"))
      (node (ref "U4") (pin "4") (pinfunction "GND_4") (pintype "power_in"))
      (node (ref "U4") (pin "7") (pinfunction "REF1_7") (pintype "input"))
      (node (ref "U6") (pin "1") (pinfunction "AIN3_1") (pintype "input"))
      (node (ref "U6") (pin "2") (pinfunction "AIN4_2") (pintype "input"))
      (node (ref "U6") (pin "21") (pinfunction "EPAD_21") (pintype "passive"))
      (node (ref "U6") (pin "3") (pinfunction "AIN5_3") (pintype "input"))
      (node (ref "U6") (pin "4") (pinfunction "AIN6_4") (pintype "input"))
      (node (ref "U6") (pin "5") (pinfunction "AIN7_5") (pintype "input"))
      (node (ref "U6") (pin "6") (pinfunction "AGND_6") (pintype "power_in"))
      (node (ref "U6") (pin "9") (pinfunction "DGND_9") (pintype "power_in"))
      (node (ref "U7") (pin "12") (pinfunction "PGND_12") (pintype "bidirectional"))
      (node (ref "U7") (pin "13") (pinfunction "PGND_13") (pintype "bidirectional"))
      (node (ref "U7") (pin "14") (pinfunction "PGND_14") (pintype "bidirectional"))
      (node (ref "U7") (pin "3") (pinfunction "AGND_3") (pintype "bidirectional"))
      (node (ref "U8") (pin "13") (pinfunction "GND_13") (pintype "bidirectional"))
      (node (ref "U9") (pin "1") (pinfunction "GND_1") (pintype "power_in"))
    )
    (net (code "42") (name "H1") (class "Default")
      (node (ref "IC2") (pin "3") (pinfunction "INA_3") (pintype "input"))
      (node (ref "J2") (pin "1") (pinfunction "1_1") (pintype "bidirectional"))
      (node (ref "J3") (pin "3") (pinfunction "3_3") (pintype "passive"))
    )
    (net (code "43") (name "H2") (class "Default")
      (node (ref "IC2") (pin "4") (pinfunction "INB_4") (pintype "input"))
      (node (ref "J2") (pin "3") (pinfunction "3_3") (pintype "bidirectional"))
      (node (ref "J3") (pin "2") (pinfunction "2_2") (pintype "passive"))
    )
    (net (code "44") (name "H3") (class "Default")
      (node (ref "IC2") (pin "5") (pinfunction "INC_5") (pintype "input"))
      (node (ref "J2") (pin "5") (pinfunction "5_5") (pintype "bidirectional"))
      (node (ref "J3") (pin "1") (pinfunction "1_1") (pintype "passive"))
    )
    (net (code "45") (name "MISO") (class "Default")
      (node (ref "IC1") (pin "11") (pinfunction "IND_11") (pintype "input"))
      (node (ref "U1") (pin "6") (pinfunction "SDO_6") (pintype "bidirectional"))
      (node (ref "U6") (pin "14") (pinfunction "DOUT_14") (pintype "bidirectional"))
    )
    (net (code "46") (name "MOSI") (class "Default")
      (node (ref "IC1") (pin "12") (pinfunction "OUTC_12") (pintype "output"))
      (node (ref "U1") (pin "5") (pinfunction "SDI_5") (pintype "bidirectional"))
      (node (ref "U6") (pin "13") (pinfunction "DIN_13") (pintype "input"))
    )
    (net (code "47") (name "Net-(D1-PadA)") (class "Default")
      (node (ref "D1") (pin "A") (pinfunction "A_A") (pintype "passive"))
      (node (ref "R9") (pin "1") (pinfunction "1_1") (pintype "passive"))
    )
    (net (code "48") (name "Net-(D4-PadA)") (class "Default")
      (node (ref "D4") (pin "A") (pinfunction "A_A") (pintype "passive"))
      (node (ref "R22") (pin "1") (pinfunction "1_1") (pintype "passive"))
    )
    (net (code "49") (name "Net-(D5-PadA)") (class "Default")
      (node (ref "D5") (pin "A") (pinfunction "A_A") (pintype "passive"))
      (node (ref "R23") (pin "2") (pinfunction "2_2") (pintype "passive"))
    )
    (net (code "50") (name "Net-(D7-PadA)") (class "Default")
      (node (ref "D7") (pin "A") (pinfunction "A_A") (pintype "passive"))
      (node (ref "R25") (pin "1") (pinfunction "1_1") (pintype "passive"))
    )
    (net (code "51") (name "Net-(S3A-A)") (class "Default")
      (node (ref "R13") (pin "1") (pinfunction "1_1") (pintype "passive"))
      (node (ref "R14") (pin "2") (pinfunction "2_2") (pintype "passive"))
      (node (ref "S3") (pin "1") (pinfunction "A_1") (pintype "bidirectional"))
    )
    (net (code "52") (name "Net-(U1-AVDD)") (class "Default")
      (node (ref "C7") (pin "1") (pinfunction "1_1") (pintype "passive"))
      (node (ref "U1") (pin "23") (pinfunction "AVDD_23") (pintype "bidirectional"))
    )
    (net (code "53") (name "Net-(U1-BST_A)") (class "Default")
      (node (ref "C4") (pin "1") (pinfunction "1_1") (pintype "passive"))
      (node (ref "U1") (pin "44") (pinfunction "BST_A_44") (pintype "bidirectional"))
    )
    (net (code "54") (name "Net-(U1-BST_B)") (class "Default")
      (node (ref "C5") (pin "1") (pinfunction "1_1") (pintype "passive"))
      (node (ref "U1") (pin "39") (pinfunction "BST_B_39") (pintype "bidirectional"))
    )
    (net (code "55") (name "Net-(U1-BST_C)") (class "Default")
      (node (ref "C6") (pin "1") (pinfunction "1_1") (pintype "passive"))
      (node (ref "U1") (pin "34") (pinfunction "BST_C_34") (pintype "bidirectional"))
    )
    (net (code "56") (name "Net-(U1-CP1)") (class "Default")
      (node (ref "C9") (pin "1") (pinfunction "1_1") (pintype "passive"))
      (node (ref "U1") (pin "10") (pinfunction "CP1_10") (pintype "bidirectional"))
    )
    (net (code "57") (name "Net-(U1-CP2)") (class "Default")
      (node (ref "C9") (pin "2") (pinfunction "2_2") (pintype "passive"))
      (node (ref "U1") (pin "11") (pinfunction "CP2_11") (pintype "bidirectional"))
    )
    (net (code "58") (name "Net-(U1-DVDD)") (class "Default")
      (node (ref "C8") (pin "1") (pinfunction "1_1") (pintype "passive"))
      (node (ref "R8") (pin "1") (pinfunction "1_1") (pintype "passive"))
      (node (ref "U1") (pin "19") (pinfunction "DVDD_19") (pintype "bidirectional"))
    )
    (net (code "59") (name "Net-(U1-EN_GATE)") (class "Default")
      (node (ref "R4") (pin "2") (pinfunction "2_2") (pintype "passive"))
      (node (ref "U1") (pin "12") (pinfunction "EN_GATE_12") (pintype "bidirectional"))
    )
    (net (code "60") (name "Net-(U1-GVDD)") (class "Default")
      (node (ref "C11") (pin "1") (pinfunction "1_1") (pintype "passive"))
      (node (ref "U1") (pin "9") (pinfunction "GVDD_9") (pintype "bidirectional"))
    )
    (net (code "61") (name "Net-(U2-OUT)") (class "Default")
      (node (ref "R5") (pin "1") (pinfunction "1_1") (pintype "passive"))
      (node (ref "TP1") (pin "TP") (pinfunction "TP_TP") (pintype "input"))
      (node (ref "U2") (pin "8") (pinfunction "OUT_8") (pintype "output"))
    )
    (net (code "62") (name "Net-(U3-OUT)") (class "Default")
      (node (ref "R6") (pin "1") (pinfunction "1_1") (pintype "passive"))
      (node (ref "TP2") (pin "TP") (pinfunction "TP_TP") (pintype "input"))
      (node (ref "U3") (pin "8") (pinfunction "OUT_8") (pintype "output"))
    )
    (net (code "63") (name "Net-(U4-OUT)") (class "Default")
      (node (ref "R7") (pin "1") (pinfunction "1_1") (pintype "passive"))
      (node (ref "TP3") (pin "TP") (pinfunction "TP_TP") (pintype "input"))
      (node (ref "U4") (pin "8") (pinfunction "OUT_8") (pintype "output"))
    )
    (net (code "64") (name "Net-(U7-AAM)") (class "Default")
      (node (ref "R15") (pin "2") (pinfunction "2_2") (pintype "passive"))
      (node (ref "U7") (pin "18") (pinfunction "AAM_18") (pintype "bidirectional"))
    )
    (net (code "65") (name "Net-(U7-EN)") (class "Default")
      (node (ref "R16") (pin "2") (pinfunction "2_2") (pintype "passive"))
      (node (ref "U7") (pin "17") (pinfunction "EN_17") (pintype "bidirectional"))
    )
    (net (code "66") (name "Net-(U7-FB)") (class "Default")
      (node (ref "R20") (pin "1") (pinfunction "1_1") (pintype "passive"))
      (node (ref "R21") (pin "2") (pinfunction "2_2") (pintype "passive"))
      (node (ref "U7") (pin "1") (pinfunction "FB_1") (pintype "bidirectional"))
    )
    (net (code "67") (name "Net-(U7-OUT)") (class "Default")
      (node (ref "C44") (pin "1") (pinfunction "1_1") (pintype "passive"))
      (node (ref "F1") (pin "1") (pinfunction "1_1") (pintype "bidirectional"))
      (node (ref "R20") (pin "2") (pinfunction "2_2") (pintype "passive"))
      (node (ref "U7") (pin "789") (pinfunction "OUT_789") (pintype "bidirectional"))
    )
    (net (code "68") (name "Net-(U8-CS1)") (class "Default")
      (node (ref "R18") (pin "2") (pinfunction "2_2") (pintype "passive"))
      (node (ref "U8") (pin "10") (pinfunction "CS1_10") (pintype "bidirectional"))
    )
    (net (code "69") (name "Net-(U8-CS2)") (class "Default")
      (node (ref "R19") (pin "2") (pinfunction "2_2") (pintype "passive"))
      (node (ref "U8") (pin "15") (pinfunction "CS2_15") (pintype "bidirectional"))
    )
    (net (code "70") (name "Net-(U8-CS_DIS)") (class "Default")
      (node (ref "R17") (pin "2") (pinfunction "2_2") (pintype "passive"))
      (node (ref "U8") (pin "12") (pinfunction "CS_DIS_12") (pintype "bidirectional"))
    )
    (net (code "71") (name "Net-(U13-EN)") (class "Default")
      (node (ref "R24") (pin "1") (pinfunction "1_1") (pintype "passive"))
      (node (ref "U13") (pin "3") (pinfunction "EN_3") (pintype "bidirectional"))
    )
    (net (code "72") (name "OCTW") (class "Default")
      (node (ref "U1") (pin "1") (pinfunction "~{OCTW}_1") (pintype "bidirectional"))
    )
    (net (code "73") (name "PHASE_A") (class "Default")
      (node (ref "J2") (pin "8") (pinfunction "8_8") (pintype "bidirectional"))
      (node (ref "J3") (pin "8") (pinfunction "8_8") (pintype "passive"))
      (node (ref "R2") (pin "2") (pinfunction "2_2") (pintype "passive"))
      (node (ref "U2") (pin "3") (pinfunction "IN-_3") (pintype "input"))
    )
    (net (code "74") (name "PHASE_B") (class "Default")
      (node (ref "J2") (pin "7") (pinfunction "7_7") (pintype "bidirectional"))
      (node (ref "J3") (pin "7") (pinfunction "7_7") (pintype "passive"))
      (node (ref "R1") (pin "2") (pinfunction "2_2") (pintype "passive"))
      (node (ref "U3") (pin "3") (pinfunction "IN-_3") (pintype "input"))
    )
    (net (code "75") (name "PHASE_C") (class "Default")
      (node (ref "J2") (pin "6") (pinfunction "6_6") (pintype "bidirectional"))
      (node (ref "J3") (pin "6") (pinfunction "6_6") (pintype "passive"))
      (node (ref "R3") (pin "2") (pinfunction "2_2") (pintype "passive"))
      (node (ref "U4") (pin "3") (pinfunction "IN-_3") (pintype "input"))
    )
    (net (code "76") (name "SCK") (class "Default")
      (node (ref "IC1") (pin "13") (pinfunction "OUTB_13") (pintype "output"))
      (node (ref "U1") (pin "7") (pinfunction "SCLK_7") (pintype "bidirectional"))
      (node (ref "U6") (pin "15") (pinfunction "SCLK_15") (pintype "input"))
    )
    (net (code "77") (name "SENSE_A") (class "Default")
      (node (ref "C22") (pin "1") (pinfunction "1_1") (pintype "passive"))
      (node (ref "R5") (pin "2") (pinfunction "2_2") (pintype "passive"))
      (node (ref "U6") (pin "20") (pinfunction "AIN2_20") (pintype "input"))
    )
    (net (code "78") (name "SENSE_B") (class "Default")
      (node (ref "C23") (pin "1") (pinfunction "1_1") (pintype "passive"))
      (node (ref "R6") (pin "2") (pinfunction "2_2") (pintype "passive"))
      (node (ref "U6") (pin "19") (pinfunction "AIN1_19") (pintype "input"))
    )
    (net (code "79") (name "SENSE_C") (class "Default")
      (node (ref "C24") (pin "1") (pinfunction "1_1") (pintype "passive"))
      (node (ref "R7") (pin "2") (pinfunction "2_2") (pintype "passive"))
      (node (ref "U6") (pin "18") (pinfunction "AIN0_18") (pintype "input"))
    )
    (net (code "80") (name "SH_A") (class "Default")
      (node (ref "C4") (pin "2") (pinfunction "2_2") (pintype "passive"))
      (node (ref "Q1") (pin "1") (pinfunction "S_1") (pintype "passive"))
      (node (ref "Q1") (pin "2") (pinfunction "S_2") (pintype "passive"))
      (node (ref "Q1") (pin "3") (pinfunction "S_3") (pintype "passive"))
      (node (ref "Q2") (pin "5678") (pinfunction "D_5678") (pintype "passive"))
      (node (ref "R2") (pin "1") (pinfunction "1_1") (pintype "passive"))
      (node (ref "U1") (pin "42") (pinfunction "SH_A_42") (pintype "bidirectional"))
      (node (ref "U2") (pin "2") (pinfunction "IN+_2") (pintype "input"))
    )
    (net (code "81") (name "SH_B") (class "Default")
      (node (ref "C5") (pin "2") (pinfunction "2_2") (pintype "passive"))
      (node (ref "Q3") (pin "1") (pinfunction "S_1") (pintype "passive"))
      (node (ref "Q3") (pin "2") (pinfunction "S_2") (pintype "passive"))
      (node (ref "Q3") (pin "3") (pinfunction "S_3") (pintype "passive"))
      (node (ref "Q4") (pin "5678") (pinfunction "D_5678") (pintype "passive"))
      (node (ref "R1") (pin "1") (pinfunction "1_1") (pintype "passive"))
      (node (ref "U1") (pin "37") (pinfunction "SH_B_37") (pintype "bidirectional"))
      (node (ref "U3") (pin "2") (pinfunction "IN+_2") (pintype "input"))
    )
    (net (code "82") (name "SH_C") (class "Default")
      (node (ref "C6") (pin "2") (pinfunction "2_2") (pintype "passive"))
      (node (ref "Q5") (pin "1") (pinfunction "S_1") (pintype "passive"))
      (node (ref "Q5") (pin "2") (pinfunction "S_2") (pintype "passive"))
      (node (ref "Q5") (pin "3") (pinfunction "S_3") (pintype "passive"))
      (node (ref "Q6") (pin "5678") (pinfunction "D_5678") (pintype "passive"))
      (node (ref "R3") (pin "1") (pinfunction "1_1") (pintype "passive"))
      (node (ref "U1") (pin "32") (pinfunction "SH_C_32") (pintype "bidirectional"))
      (node (ref "U4") (pin "2") (pinfunction "IN+_2") (pintype "input"))
    )
    (net (code "83") (name "VBATT") (class "Default")
      (node (ref "U8") (pin "1") (pinfunction "OUT2_1") (pintype "bidirectional"))
      (node (ref "U8") (pin "2") (pinfunction "OUT2_2") (pintype "bidirectional"))
      (node (ref "U8") (pin "3") (pinfunction "OUT2_3") (pintype "bidirectional"))
      (node (ref "U8") (pin "4") (pinfunction "OUT2_4") (pintype "bidirectional"))
      (node (ref "U8") (pin "5") (pinfunction "OUT1_5") (pintype "bidirectional"))
      (node (ref "U8") (pin "6") (pinfunction "OUT1_6") (pintype "bidirectional"))
      (node (ref "U8") (pin "7") (pinfunction "OUT1_7") (pintype "bidirectional"))
      (node (ref "U8") (pin "8") (pinfunction "OUT1_8") (pintype "bidirectional"))
      (node (ref "XF1") (pin "1") (pinfunction "1_1") (pintype "bidirectional"))
      (node (ref "XF1") (pin "2") (pinfunction "1_2") (pintype "bidirectional"))
    )
    (net (code "84") (name "VIN") (class "Default")
      (node (ref "J6") (pin "1") (pinfunction "1_1") (pintype "bidirectional"))
      (node (ref "R13") (pin "2") (pinfunction "2_2") (pintype "passive"))
      (node (ref "U8") (pin "17") (pinfunction "VCC_17") (pintype "bidirectional"))
    )
    (net (code "85") (name "unconnected-(IC4-NC-Pad7)") (class "Default")
      (node (ref "IC4") (pin "7") (pinfunction "NC_7") (pintype "no_connect"))
    )
    (net (code "86") (name "unconnected-(U1-SN1-Pad29)") (class "Default")
      (node (ref "U1") (pin "29") (pinfunction "SN1_29") (pintype "bidirectional"))
    )
    (net (code "87") (name "unconnected-(U1-SN2-Pad27)") (class "Default")
      (node (ref "U1") (pin "27") (pinfunction "SN2_27") (pintype "bidirectional"))
    )
    (net (code "88") (name "unconnected-(U1-SO1-Pad21)") (class "Default")
      (node (ref "U1") (pin "21") (pinfunction "SO1_21") (pintype "bidirectional"))
    )
    (net (code "89") (name "unconnected-(U1-SO2-Pad22)") (class "Default")
      (node (ref "U1") (pin "22") (pinfunction "SO2_22") (pintype "bidirectional"))
    )
    (net (code "90") (name "unconnected-(U1-SP1-Pad28)") (class "Default")
      (node (ref "U1") (pin "28") (pinfunction "SP1_28") (pintype "bidirectional"))
    )
    (net (code "91") (name "unconnected-(U1-SP2-Pad26)") (class "Default")
      (node (ref "U1") (pin "26") (pinfunction "SP2_26") (pintype "bidirectional"))
    )
    (net (code "92") (name "unconnected-(U2-NC-Pad1)") (class "Default")
      (node (ref "U2") (pin "1") (pinfunction "NC_1") (pintype "passive"))
    )
    (net (code "93") (name "unconnected-(U3-NC-Pad1)") (class "Default")
      (node (ref "U3") (pin "1") (pinfunction "NC_1") (pintype "passive"))
    )
    (net (code "94") (name "unconnected-(U4-NC-Pad1)") (class "Default")
      (node (ref "U4") (pin "1") (pinfunction "NC_1") (pintype "passive"))
    )
    (net (code "95") (name "unconnected-(U6-NC-Pad8)") (class "Default")
      (node (ref "U6") (pin "8") (pinfunction "NC_8") (pintype "no_connect"))
    )
    (net (code "96") (name "unconnected-(U6-TM_BUSY-Pad12)") (class "Default")
      (node (ref "U6") (pin "12") (pinfunction "TM_BUSY_12") (pintype "output"))
    )
    (net (code "97") (name "unconnected-(U7-BST-Pad11)") (class "Default")
      (node (ref "U7") (pin "11") (pinfunction "BST_11") (pintype "bidirectional"))
    )
    (net (code "98") (name "unconnected-(U7-SW-Pad456)") (class "Default")
      (node (ref "U7") (pin "456") (pinfunction "SW_456") (pintype "bidirectional"))
    )
    (net (code "99") (name "unconnected-(U7-VCC-Pad2)") (class "Default")
      (node (ref "U7") (pin "2") (pinfunction "VCC_2") (pintype "bidirectional"))
    )
  )
)
